# LE1-11.net
KiCad netlist of a schematic drawn in EAGLE
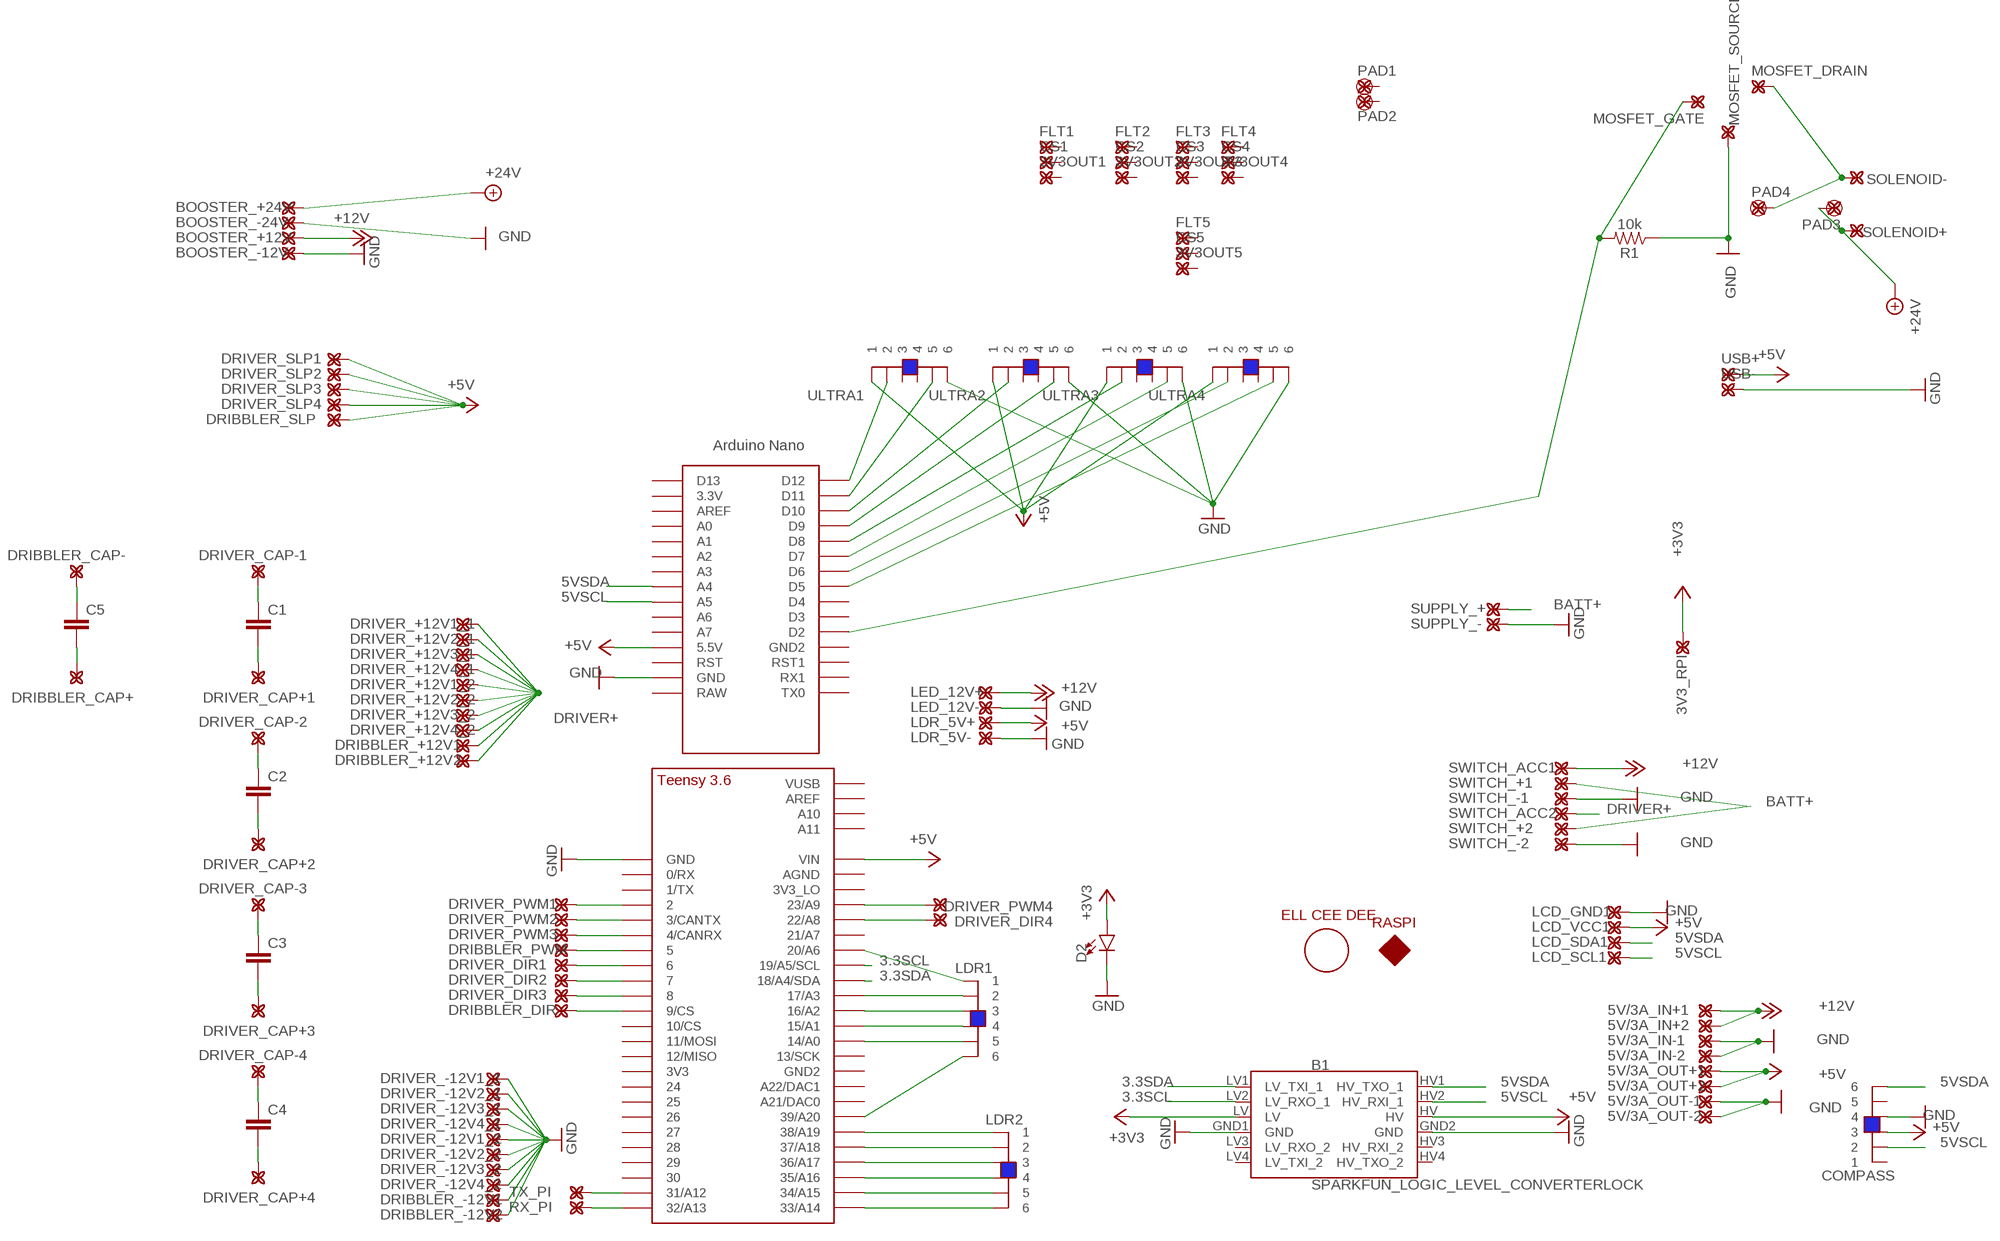
[diagram p0: schematic, sheet 1]

(export (version "E")
  (design (tool "Eeschema 10.0.6"))
  (components
    (comp (ref "3V3OUT1")
      (value "BETTERPAD_2.54")
      (footprint "eagle-import:SUPERIORSIM")
      (libsource (lib "eagle-import") (part "BETTERPAD_2.54"))
    )
    (comp (ref "3V3OUT2")
      (value "BETTERPAD_2.54")
      (footprint "eagle-import:SUPERIORSIM")
      (libsource (lib "eagle-import") (part "BETTERPAD_2.54"))
    )
    (comp (ref "3V3OUT3")
      (value "BETTERPAD_2.54")
      (footprint "eagle-import:SUPERIORSIM")
      (libsource (lib "eagle-import") (part "BETTERPAD_2.54"))
    )
    (comp (ref "3V3OUT4")
      (value "BETTERPAD_2.54")
      (footprint "eagle-import:SUPERIORSIM")
      (libsource (lib "eagle-import") (part "BETTERPAD_2.54"))
    )
    (comp (ref "3V3OUT5")
      (value "BETTERPAD_2.54")
      (footprint "eagle-import:SUPERIORSIM")
      (libsource (lib "eagle-import") (part "BETTERPAD_2.54"))
    )
    (comp (ref "3V3_RPI")
      (value "BETTERPAD_2.54")
      (footprint "eagle-import:SUPERIORSIM")
      (libsource (lib "eagle-import") (part "BETTERPAD_2.54"))
    )
    (comp (ref "5V/3A_IN+1")
      (value "BETTERPAD_2.54")
      (footprint "eagle-import:SUPERIORSIM")
      (libsource (lib "eagle-import") (part "BETTERPAD_2.54"))
    )
    (comp (ref "5V/3A_IN+2")
      (value "BETTERPAD_2.54")
      (footprint "eagle-import:SUPERIORSIM")
      (libsource (lib "eagle-import") (part "BETTERPAD_2.54"))
    )
    (comp (ref "5V/3A_IN-1")
      (value "BETTERPAD_2.54")
      (footprint "eagle-import:SUPERIORSIM")
      (libsource (lib "eagle-import") (part "BETTERPAD_2.54"))
    )
    (comp (ref "5V/3A_IN-2")
      (value "BETTERPAD_2.54")
      (footprint "eagle-import:SUPERIORSIM")
      (libsource (lib "eagle-import") (part "BETTERPAD_2.54"))
    )
    (comp (ref "5V/3A_OUT+1")
      (value "BETTERPAD_2.54")
      (footprint "eagle-import:SUPERIORSIM")
      (libsource (lib "eagle-import") (part "BETTERPAD_2.54"))
    )
    (comp (ref "5V/3A_OUT+2")
      (value "BETTERPAD_2.54")
      (footprint "eagle-import:SUPERIORSIM")
      (libsource (lib "eagle-import") (part "BETTERPAD_2.54"))
    )
    (comp (ref "5V/3A_OUT-1")
      (value "BETTERPAD_2.54")
      (footprint "eagle-import:SUPERIORSIM")
      (libsource (lib "eagle-import") (part "BETTERPAD_2.54"))
    )
    (comp (ref "5V/3A_OUT-2")
      (value "BETTERPAD_2.54")
      (footprint "eagle-import:SUPERIORSIM")
      (libsource (lib "eagle-import") (part "BETTERPAD_2.54"))
    )
    (comp (ref "B1")
      (value "SPARKFUN_LOGIC_LEVEL_CONVERTERLOCK")
      (footprint "eagle-import:SPARKFUN_LOGIC_LEVEL_CONVERTER_LOCK")
      (libsource (lib "eagle-import") (part "SPARKFUN_LOGIC_LEVEL_CONVERTERLOCK"))
    )
    (comp (ref "BOOSTER_+12V")
      (value "BETTERPAD_2.54")
      (footprint "eagle-import:SUPERIORSIM")
      (libsource (lib "eagle-import") (part "BETTERPAD_2.54"))
    )
    (comp (ref "BOOSTER_+24V")
      (value "BETTERPAD_2.54")
      (footprint "eagle-import:SUPERIORSIM")
      (libsource (lib "eagle-import") (part "BETTERPAD_2.54"))
    )
    (comp (ref "BOOSTER_-12V")
      (value "BETTERPAD_2.54")
      (footprint "eagle-import:SUPERIORSIM")
      (libsource (lib "eagle-import") (part "BETTERPAD_2.54"))
    )
    (comp (ref "BOOSTER_-24V")
      (value "BETTERPAD_2.54")
      (footprint "eagle-import:SUPERIORSIM")
      (libsource (lib "eagle-import") (part "BETTERPAD_2.54"))
    )
    (comp (ref "C1")
      (value "C5/7.2")
      (footprint "eagle-import:C5B7.2")
      (libsource (lib "eagle-import") (part "C5/7.2"))
    )
    (comp (ref "C2")
      (value "C5/7.2")
      (footprint "eagle-import:C5B7.2")
      (libsource (lib "eagle-import") (part "C5/7.2"))
    )
    (comp (ref "C3")
      (value "C5/7.2")
      (footprint "eagle-import:C5B7.2")
      (libsource (lib "eagle-import") (part "C5/7.2"))
    )
    (comp (ref "C4")
      (value "C5/7.2")
      (footprint "eagle-import:C5B7.2")
      (libsource (lib "eagle-import") (part "C5/7.2"))
    )
    (comp (ref "C5")
      (value "C5/7.2")
      (footprint "eagle-import:C5B7.2")
      (libsource (lib "eagle-import") (part "C5/7.2"))
    )
    (comp (ref "COMPASS")
      (value "6P6C_FEMALESMD")
      (footprint "eagle-import:6P6C_FEMALE")
      (libsource (lib "eagle-import") (part "6P6C_FEMALESMD"))
    )
    (comp (ref "CS1")
      (value "BETTERPAD_2.54")
      (footprint "eagle-import:SUPERIORSIM")
      (libsource (lib "eagle-import") (part "BETTERPAD_2.54"))
    )
    (comp (ref "CS2")
      (value "BETTERPAD_2.54")
      (footprint "eagle-import:SUPERIORSIM")
      (libsource (lib "eagle-import") (part "BETTERPAD_2.54"))
    )
    (comp (ref "CS3")
      (value "BETTERPAD_2.54")
      (footprint "eagle-import:SUPERIORSIM")
      (libsource (lib "eagle-import") (part "BETTERPAD_2.54"))
    )
    (comp (ref "CS4")
      (value "BETTERPAD_2.54")
      (footprint "eagle-import:SUPERIORSIM")
      (libsource (lib "eagle-import") (part "BETTERPAD_2.54"))
    )
    (comp (ref "CS5")
      (value "BETTERPAD_2.54")
      (footprint "eagle-import:SUPERIORSIM")
      (libsource (lib "eagle-import") (part "BETTERPAD_2.54"))
    )
    (comp (ref "D2")
      (value "LED-3MM-NO_SILK")
      (footprint "eagle-import:LED_3MM-NS")
      (libsource (lib "eagle-import") (part "LED-3MM-NO_SILK"))
    )
    (comp (ref "DRIBBLER_+12V1")
      (value "BETTERPAD_2.54")
      (footprint "eagle-import:SUPERIORSIM")
      (libsource (lib "eagle-import") (part "BETTERPAD_2.54"))
    )
    (comp (ref "DRIBBLER_+12V2")
      (value "BETTERPAD_2.54")
      (footprint "eagle-import:SUPERIORSIM")
      (libsource (lib "eagle-import") (part "BETTERPAD_2.54"))
    )
    (comp (ref "DRIBBLER_-12V1")
      (value "BETTERPAD_2.54")
      (footprint "eagle-import:SUPERIORSIM")
      (libsource (lib "eagle-import") (part "BETTERPAD_2.54"))
    )
    (comp (ref "DRIBBLER_-12V2")
      (value "BETTERPAD_2.54")
      (footprint "eagle-import:SUPERIORSIM")
      (libsource (lib "eagle-import") (part "BETTERPAD_2.54"))
    )
    (comp (ref "DRIBBLER_CAP+")
      (value "BETTERPAD_2.54")
      (footprint "eagle-import:SUPERIORSIM")
      (libsource (lib "eagle-import") (part "BETTERPAD_2.54"))
    )
    (comp (ref "DRIBBLER_CAP-")
      (value "BETTERPAD_2.54")
      (footprint "eagle-import:SUPERIORSIM")
      (libsource (lib "eagle-import") (part "BETTERPAD_2.54"))
    )
    (comp (ref "DRIBBLER_DIR")
      (value "BETTERPAD_2.54")
      (footprint "eagle-import:SUPERIORSIM")
      (libsource (lib "eagle-import") (part "BETTERPAD_2.54"))
    )
    (comp (ref "DRIBBLER_PWM")
      (value "BETTERPAD_2.54")
      (footprint "eagle-import:SUPERIORSIM")
      (libsource (lib "eagle-import") (part "BETTERPAD_2.54"))
    )
    (comp (ref "DRIBBLER_SLP")
      (value "BETTERPAD_2.54")
      (footprint "eagle-import:SUPERIORSIM")
      (libsource (lib "eagle-import") (part "BETTERPAD_2.54"))
    )
    (comp (ref "DRIVER_+12V1_1")
      (value "BETTERPAD_2.54")
      (footprint "eagle-import:SUPERIORSIM")
      (libsource (lib "eagle-import") (part "BETTERPAD_2.54"))
    )
    (comp (ref "DRIVER_+12V1_2")
      (value "BETTERPAD_2.54")
      (footprint "eagle-import:SUPERIORSIM")
      (libsource (lib "eagle-import") (part "BETTERPAD_2.54"))
    )
    (comp (ref "DRIVER_+12V2_1")
      (value "BETTERPAD_2.54")
      (footprint "eagle-import:SUPERIORSIM")
      (libsource (lib "eagle-import") (part "BETTERPAD_2.54"))
    )
    (comp (ref "DRIVER_+12V2_2")
      (value "BETTERPAD_2.54")
      (footprint "eagle-import:SUPERIORSIM")
      (libsource (lib "eagle-import") (part "BETTERPAD_2.54"))
    )
    (comp (ref "DRIVER_+12V3_1")
      (value "BETTERPAD_2.54")
      (footprint "eagle-import:SUPERIORSIM")
      (libsource (lib "eagle-import") (part "BETTERPAD_2.54"))
    )
    (comp (ref "DRIVER_+12V3_2")
      (value "BETTERPAD_2.54")
      (footprint "eagle-import:SUPERIORSIM")
      (libsource (lib "eagle-import") (part "BETTERPAD_2.54"))
    )
    (comp (ref "DRIVER_+12V4_1")
      (value "BETTERPAD_2.54")
      (footprint "eagle-import:SUPERIORSIM")
      (libsource (lib "eagle-import") (part "BETTERPAD_2.54"))
    )
    (comp (ref "DRIVER_+12V4_2")
      (value "BETTERPAD_2.54")
      (footprint "eagle-import:SUPERIORSIM")
      (libsource (lib "eagle-import") (part "BETTERPAD_2.54"))
    )
    (comp (ref "DRIVER_-12V1_1")
      (value "BETTERPAD_2.54")
      (footprint "eagle-import:SUPERIORSIM")
      (libsource (lib "eagle-import") (part "BETTERPAD_2.54"))
    )
    (comp (ref "DRIVER_-12V1_2")
      (value "BETTERPAD_2.54")
      (footprint "eagle-import:SUPERIORSIM")
      (libsource (lib "eagle-import") (part "BETTERPAD_2.54"))
    )
    (comp (ref "DRIVER_-12V2_1")
      (value "BETTERPAD_2.54")
      (footprint "eagle-import:SUPERIORSIM")
      (libsource (lib "eagle-import") (part "BETTERPAD_2.54"))
    )
    (comp (ref "DRIVER_-12V2_2")
      (value "BETTERPAD_2.54")
      (footprint "eagle-import:SUPERIORSIM")
      (libsource (lib "eagle-import") (part "BETTERPAD_2.54"))
    )
    (comp (ref "DRIVER_-12V3_1")
      (value "BETTERPAD_2.54")
      (footprint "eagle-import:SUPERIORSIM")
      (libsource (lib "eagle-import") (part "BETTERPAD_2.54"))
    )
    (comp (ref "DRIVER_-12V3_2")
      (value "BETTERPAD_2.54")
      (footprint "eagle-import:SUPERIORSIM")
      (libsource (lib "eagle-import") (part "BETTERPAD_2.54"))
    )
    (comp (ref "DRIVER_-12V4_1")
      (value "BETTERPAD_2.54")
      (footprint "eagle-import:SUPERIORSIM")
      (libsource (lib "eagle-import") (part "BETTERPAD_2.54"))
    )
    (comp (ref "DRIVER_-12V4_2")
      (value "BETTERPAD_2.54")
      (footprint "eagle-import:SUPERIORSIM")
      (libsource (lib "eagle-import") (part "BETTERPAD_2.54"))
    )
    (comp (ref "DRIVER_CAP+1")
      (value "BETTERPAD_2.54")
      (footprint "eagle-import:SUPERIORSIM")
      (libsource (lib "eagle-import") (part "BETTERPAD_2.54"))
    )
    (comp (ref "DRIVER_CAP+2")
      (value "BETTERPAD_2.54")
      (footprint "eagle-import:SUPERIORSIM")
      (libsource (lib "eagle-import") (part "BETTERPAD_2.54"))
    )
    (comp (ref "DRIVER_CAP+3")
      (value "BETTERPAD_2.54")
      (footprint "eagle-import:SUPERIORSIM")
      (libsource (lib "eagle-import") (part "BETTERPAD_2.54"))
    )
    (comp (ref "DRIVER_CAP+4")
      (value "BETTERPAD_2.54")
      (footprint "eagle-import:SUPERIORSIM")
      (libsource (lib "eagle-import") (part "BETTERPAD_2.54"))
    )
    (comp (ref "DRIVER_CAP-1")
      (value "BETTERPAD_2.54")
      (footprint "eagle-import:SUPERIORSIM")
      (libsource (lib "eagle-import") (part "BETTERPAD_2.54"))
    )
    (comp (ref "DRIVER_CAP-2")
      (value "BETTERPAD_2.54")
      (footprint "eagle-import:SUPERIORSIM")
      (libsource (lib "eagle-import") (part "BETTERPAD_2.54"))
    )
    (comp (ref "DRIVER_CAP-3")
      (value "BETTERPAD_2.54")
      (footprint "eagle-import:SUPERIORSIM")
      (libsource (lib "eagle-import") (part "BETTERPAD_2.54"))
    )
    (comp (ref "DRIVER_CAP-4")
      (value "BETTERPAD_2.54")
      (footprint "eagle-import:SUPERIORSIM")
      (libsource (lib "eagle-import") (part "BETTERPAD_2.54"))
    )
    (comp (ref "DRIVER_DIR1")
      (value "BETTERPAD_2.54")
      (footprint "eagle-import:SUPERIORSIM")
      (libsource (lib "eagle-import") (part "BETTERPAD_2.54"))
    )
    (comp (ref "DRIVER_DIR2")
      (value "BETTERPAD_2.54")
      (footprint "eagle-import:SUPERIORSIM")
      (libsource (lib "eagle-import") (part "BETTERPAD_2.54"))
    )
    (comp (ref "DRIVER_DIR3")
      (value "BETTERPAD_2.54")
      (footprint "eagle-import:SUPERIORSIM")
      (libsource (lib "eagle-import") (part "BETTERPAD_2.54"))
    )
    (comp (ref "DRIVER_DIR4")
      (value "BETTERPAD_2.54")
      (footprint "eagle-import:SUPERIORSIM")
      (libsource (lib "eagle-import") (part "BETTERPAD_2.54"))
    )
    (comp (ref "DRIVER_PWM1")
      (value "BETTERPAD_2.54")
      (footprint "eagle-import:SUPERIORSIM")
      (libsource (lib "eagle-import") (part "BETTERPAD_2.54"))
    )
    (comp (ref "DRIVER_PWM2")
      (value "BETTERPAD_2.54")
      (footprint "eagle-import:SUPERIORSIM")
      (libsource (lib "eagle-import") (part "BETTERPAD_2.54"))
    )
    (comp (ref "DRIVER_PWM3")
      (value "BETTERPAD_2.54")
      (footprint "eagle-import:SUPERIORSIM")
      (libsource (lib "eagle-import") (part "BETTERPAD_2.54"))
    )
    (comp (ref "DRIVER_PWM4")
      (value "BETTERPAD_2.54")
      (footprint "eagle-import:SUPERIORSIM")
      (libsource (lib "eagle-import") (part "BETTERPAD_2.54"))
    )
    (comp (ref "DRIVER_SLP1")
      (value "BETTERPAD_2.54")
      (footprint "eagle-import:SUPERIORSIM")
      (libsource (lib "eagle-import") (part "BETTERPAD_2.54"))
    )
    (comp (ref "DRIVER_SLP2")
      (value "BETTERPAD_2.54")
      (footprint "eagle-import:SUPERIORSIM")
      (libsource (lib "eagle-import") (part "BETTERPAD_2.54"))
    )
    (comp (ref "DRIVER_SLP3")
      (value "BETTERPAD_2.54")
      (footprint "eagle-import:SUPERIORSIM")
      (libsource (lib "eagle-import") (part "BETTERPAD_2.54"))
    )
    (comp (ref "DRIVER_SLP4")
      (value "BETTERPAD_2.54")
      (footprint "eagle-import:SUPERIORSIM")
      (libsource (lib "eagle-import") (part "BETTERPAD_2.54"))
    )
    (comp (ref "FLT1")
      (value "BETTERPAD_2.54")
      (footprint "eagle-import:SUPERIORSIM")
      (libsource (lib "eagle-import") (part "BETTERPAD_2.54"))
    )
    (comp (ref "FLT2")
      (value "BETTERPAD_2.54")
      (footprint "eagle-import:SUPERIORSIM")
      (libsource (lib "eagle-import") (part "BETTERPAD_2.54"))
    )
    (comp (ref "FLT3")
      (value "BETTERPAD_2.54")
      (footprint "eagle-import:SUPERIORSIM")
      (libsource (lib "eagle-import") (part "BETTERPAD_2.54"))
    )
    (comp (ref "FLT4")
      (value "BETTERPAD_2.54")
      (footprint "eagle-import:SUPERIORSIM")
      (libsource (lib "eagle-import") (part "BETTERPAD_2.54"))
    )
    (comp (ref "FLT5")
      (value "BETTERPAD_2.54")
      (footprint "eagle-import:SUPERIORSIM")
      (libsource (lib "eagle-import") (part "BETTERPAD_2.54"))
    )
    (comp (ref "LCD1")
      (value "LCD-16X2SILK")
      (footprint "eagle-import:LCD-16X2")
      (libsource (lib "eagle-import") (part "LCD-16X2SILK"))
    )
    (comp (ref "LCD_GND1")
      (value "BETTERPAD_2.54")
      (footprint "eagle-import:SUPERIORSIM")
      (libsource (lib "eagle-import") (part "BETTERPAD_2.54"))
    )
    (comp (ref "LCD_SCL1")
      (value "BETTERPAD_2.54")
      (footprint "eagle-import:SUPERIORSIM")
      (libsource (lib "eagle-import") (part "BETTERPAD_2.54"))
    )
    (comp (ref "LCD_SDA1")
      (value "BETTERPAD_2.54")
      (footprint "eagle-import:SUPERIORSIM")
      (libsource (lib "eagle-import") (part "BETTERPAD_2.54"))
    )
    (comp (ref "LCD_VCC1")
      (value "BETTERPAD_2.54")
      (footprint "eagle-import:SUPERIORSIM")
      (libsource (lib "eagle-import") (part "BETTERPAD_2.54"))
    )
    (comp (ref "LDR1")
      (value "6P6C_FEMALESMD")
      (footprint "eagle-import:6P6C_FEMALE")
      (libsource (lib "eagle-import") (part "6P6C_FEMALESMD"))
    )
    (comp (ref "LDR2")
      (value "6P6C_FEMALESMD")
      (footprint "eagle-import:6P6C_FEMALE")
      (libsource (lib "eagle-import") (part "6P6C_FEMALESMD"))
    )
    (comp (ref "LDR_5V+")
      (value "BETTERPAD_2.54")
      (footprint "eagle-import:SUPERIORSIM")
      (libsource (lib "eagle-import") (part "BETTERPAD_2.54"))
    )
    (comp (ref "LDR_5V-")
      (value "BETTERPAD_2.54")
      (footprint "eagle-import:SUPERIORSIM")
      (libsource (lib "eagle-import") (part "BETTERPAD_2.54"))
    )
    (comp (ref "LED_12V+")
      (value "BETTERPAD_2.54")
      (footprint "eagle-import:SUPERIORSIM")
      (libsource (lib "eagle-import") (part "BETTERPAD_2.54"))
    )
    (comp (ref "LED_12V-")
      (value "BETTERPAD_2.54")
      (footprint "eagle-import:SUPERIORSIM")
      (libsource (lib "eagle-import") (part "BETTERPAD_2.54"))
    )
    (comp (ref "MOSFET_DRAIN")
      (value "BETTERPAD_2.54")
      (footprint "eagle-import:SUPERIORSIM")
      (libsource (lib "eagle-import") (part "BETTERPAD_2.54"))
    )
    (comp (ref "MOSFET_GATE")
      (value "BETTERPAD_2.54")
      (footprint "eagle-import:SUPERIORSIM")
      (libsource (lib "eagle-import") (part "BETTERPAD_2.54"))
    )
    (comp (ref "MOSFET_SOURCE")
      (value "BETTERPAD_2.54")
      (footprint "eagle-import:SUPERIORSIM")
      (libsource (lib "eagle-import") (part "BETTERPAD_2.54"))
    )
    (comp (ref "PAD1")
      (value "BETTERPAD_2.54/1.5")
      (footprint "eagle-import:1,5")
      (libsource (lib "eagle-import") (part "BETTERPAD_2.54/1.5"))
    )
    (comp (ref "PAD2")
      (value "BETTERPAD_2.54/1.5")
      (footprint "eagle-import:1,5")
      (libsource (lib "eagle-import") (part "BETTERPAD_2.54/1.5"))
    )
    (comp (ref "PAD3")
      (value "BETTERPAD_2.54/1.5")
      (footprint "eagle-import:1,5")
      (libsource (lib "eagle-import") (part "BETTERPAD_2.54/1.5"))
    )
    (comp (ref "PAD4")
      (value "BETTERPAD_2.54/1.5")
      (footprint "eagle-import:1,5")
      (libsource (lib "eagle-import") (part "BETTERPAD_2.54/1.5"))
    )
    (comp (ref "PCB1")
      (value "RPI3")
      (footprint "eagle-import:RPI3")
      (libsource (lib "eagle-import") (part "RPI3"))
    )
    (comp (ref "R1")
      (value "10k")
      (footprint "eagle-import:AXIAL-0.3")
      (libsource (lib "eagle-import") (part "10KOHM-HORIZ-1/4W-1%"))
    )
    (comp (ref "RX_PI")
      (value "BETTERPAD_2.54")
      (footprint "eagle-import:SUPERIORSIM")
      (libsource (lib "eagle-import") (part "BETTERPAD_2.54"))
    )
    (comp (ref "SOLENOID+")
      (value "BETTERPAD_2.54")
      (footprint "eagle-import:SUPERIORSIM")
      (libsource (lib "eagle-import") (part "BETTERPAD_2.54"))
    )
    (comp (ref "SOLENOID-")
      (value "BETTERPAD_2.54")
      (footprint "eagle-import:SUPERIORSIM")
      (libsource (lib "eagle-import") (part "BETTERPAD_2.54"))
    )
    (comp (ref "SUPPLY_+")
      (value "BETTERPAD_2.54")
      (footprint "eagle-import:SUPERIORSIM")
      (libsource (lib "eagle-import") (part "BETTERPAD_2.54"))
    )
    (comp (ref "SUPPLY_-")
      (value "BETTERPAD_2.54")
      (footprint "eagle-import:SUPERIORSIM")
      (libsource (lib "eagle-import") (part "BETTERPAD_2.54"))
    )
    (comp (ref "SWITCH_+1")
      (value "BETTERPAD_2.54")
      (footprint "eagle-import:SUPERIORSIM")
      (libsource (lib "eagle-import") (part "BETTERPAD_2.54"))
    )
    (comp (ref "SWITCH_+2")
      (value "BETTERPAD_2.54")
      (footprint "eagle-import:SUPERIORSIM")
      (libsource (lib "eagle-import") (part "BETTERPAD_2.54"))
    )
    (comp (ref "SWITCH_-1")
      (value "BETTERPAD_2.54")
      (footprint "eagle-import:SUPERIORSIM")
      (libsource (lib "eagle-import") (part "BETTERPAD_2.54"))
    )
    (comp (ref "SWITCH_-2")
      (value "BETTERPAD_2.54")
      (footprint "eagle-import:SUPERIORSIM")
      (libsource (lib "eagle-import") (part "BETTERPAD_2.54"))
    )
    (comp (ref "SWITCH_ACC1")
      (value "BETTERPAD_2.54")
      (footprint "eagle-import:SUPERIORSIM")
      (libsource (lib "eagle-import") (part "BETTERPAD_2.54"))
    )
    (comp (ref "SWITCH_ACC2")
      (value "BETTERPAD_2.54")
      (footprint "eagle-import:SUPERIORSIM")
      (libsource (lib "eagle-import") (part "BETTERPAD_2.54"))
    )
    (comp (ref "TX_PI")
      (value "BETTERPAD_2.54")
      (footprint "eagle-import:SUPERIORSIM")
      (libsource (lib "eagle-import") (part "BETTERPAD_2.54"))
    )
    (comp (ref "U$1")
      (value "TEENSY_3.5/3.6_BASIC")
      (footprint "eagle-import:TEENSY_3.5_3.6_BASIC")
      (libsource (lib "eagle-import") (part "TEENSY_3.5/3.6_BASIC"))
    )
    (comp (ref "U$2")
      (value "NANO")
      (footprint "eagle-import:NANO")
      (libsource (lib "eagle-import") (part "NANO"))
    )
    (comp (ref "ULTRA1")
      (value "6P6C_FEMALESMD")
      (footprint "eagle-import:6P6C_FEMALE")
      (libsource (lib "eagle-import") (part "6P6C_FEMALESMD"))
    )
    (comp (ref "ULTRA2")
      (value "6P6C_FEMALESMD")
      (footprint "eagle-import:6P6C_FEMALE")
      (libsource (lib "eagle-import") (part "6P6C_FEMALESMD"))
    )
    (comp (ref "ULTRA3")
      (value "6P6C_FEMALESMD")
      (footprint "eagle-import:6P6C_FEMALE")
      (libsource (lib "eagle-import") (part "6P6C_FEMALESMD"))
    )
    (comp (ref "ULTRA4")
      (value "6P6C_FEMALESMD")
      (footprint "eagle-import:6P6C_FEMALE")
      (libsource (lib "eagle-import") (part "6P6C_FEMALESMD"))
    )
    (comp (ref "USB+")
      (value "BETTERPAD_2.54")
      (footprint "eagle-import:SUPERIORSIM")
      (libsource (lib "eagle-import") (part "BETTERPAD_2.54"))
    )
    (comp (ref "USB-")
      (value "BETTERPAD_2.54")
      (footprint "eagle-import:SUPERIORSIM")
      (libsource (lib "eagle-import") (part "BETTERPAD_2.54"))
    )
  )
  (nets
    (net (code "1") (name "+3V3") (class "Default")
      (node (ref "3V3_RPI") (pin ".") (pinfunction "P_.") (pintype "passive"))
      (node (ref "B1") (pin "LV") (pinfunction "LV_LV") (pintype "power_in"))
      (node (ref "D2") (pin "A") (pinfunction "A_A") (pintype "passive"))
    )
    (net (code "2") (name "+5V") (class "Default")
      (node (ref "5V/3A_OUT+1") (pin ".") (pinfunction "P_.") (pintype "passive"))
      (node (ref "5V/3A_OUT+2") (pin ".") (pinfunction "P_.") (pintype "passive"))
      (node (ref "B1") (pin "HV") (pinfunction "HV_HV") (pintype "power_in"))
      (node (ref "COMPASS") (pin "3") (pinfunction "3_3") (pintype "bidirectional"))
      (node (ref "DRIBBLER_SLP") (pin ".") (pinfunction "P_.") (pintype "passive"))
      (node (ref "DRIVER_SLP1") (pin ".") (pinfunction "P_.") (pintype "passive"))
      (node (ref "DRIVER_SLP2") (pin ".") (pinfunction "P_.") (pintype "passive"))
      (node (ref "DRIVER_SLP3") (pin ".") (pinfunction "P_.") (pintype "passive"))
      (node (ref "DRIVER_SLP4") (pin ".") (pinfunction "P_.") (pintype "passive"))
      (node (ref "LCD_VCC1") (pin ".") (pinfunction "P_.") (pintype "passive"))
      (node (ref "LDR_5V+") (pin ".") (pinfunction "P_.") (pintype "passive"))
      (node (ref "U$1") (pin "VIN") (pinfunction "VIN_VIN") (pintype "bidirectional"))
      (node (ref "U$2") (pin "5V") (pinfunction "5.5V_5V") (pintype "bidirectional"))
      (node (ref "ULTRA1") (pin "1") (pinfunction "1_1") (pintype "bidirectional"))
      (node (ref "ULTRA2") (pin "1") (pinfunction "1_1") (pintype "bidirectional"))
      (node (ref "ULTRA3") (pin "1") (pinfunction "1_1") (pintype "bidirectional"))
      (node (ref "ULTRA4") (pin "1") (pinfunction "1_1") (pintype "bidirectional"))
      (node (ref "USB+") (pin ".") (pinfunction "P_.") (pintype "passive"))
    )
    (net (code "3") (name "+12V") (class "Default")
      (node (ref "5V/3A_IN+1") (pin ".") (pinfunction "P_.") (pintype "passive"))
      (node (ref "5V/3A_IN+2") (pin ".") (pinfunction "P_.") (pintype "passive"))
      (node (ref "BOOSTER_+12V") (pin ".") (pinfunction "P_.") (pintype "passive"))
      (node (ref "LED_12V+") (pin ".") (pinfunction "P_.") (pintype "passive"))
      (node (ref "SWITCH_ACC1") (pin ".") (pinfunction "P_.") (pintype "passive"))
    )
    (net (code "4") (name "+24V") (class "Default")
      (node (ref "BOOSTER_+24V") (pin ".") (pinfunction "P_.") (pintype "passive"))
      (node (ref "PAD3") (pin "P$1") (pinfunction "P_P$1") (pintype "passive"))
      (node (ref "SOLENOID+") (pin ".") (pinfunction "P_.") (pintype "passive"))
    )
    (net (code "5") (name "/3.3SCL") (class "Default")
      (node (ref "B1") (pin "LV2") (pinfunction "LV_RXO_1_LV2") (pintype "bidirectional"))
      (node (ref "U$1") (pin "19/A5/SCL") (pinfunction "19/A5/SCL_19/A5/SCL") (pintype "bidirectional"))
    )
    (net (code "6") (name "/3.3SDA") (class "Default")
      (node (ref "B1") (pin "LV1") (pinfunction "LV_TXI_1_LV1") (pintype "bidirectional"))
      (node (ref "U$1") (pin "18/A4/SDA") (pinfunction "18/A4/SDA_18/A4/SDA") (pintype "bidirectional"))
    )
    (net (code "7") (name "/5VSCL") (class "Default")
      (node (ref "B1") (pin "HV2") (pinfunction "HV_RXI_1_HV2") (pintype "bidirectional"))
      (node (ref "COMPASS") (pin "2") (pinfunction "2_2") (pintype "bidirectional"))
      (node (ref "LCD_SCL1") (pin ".") (pinfunction "P_.") (pintype "passive"))
      (node (ref "U$2") (pin "A5") (pinfunction "A5_A5") (pintype "bidirectional"))
    )
    (net (code "8") (name "/5VSDA") (class "Default")
      (node (ref "B1") (pin "HV1") (pinfunction "HV_TXO_1_HV1") (pintype "bidirectional"))
      (node (ref "COMPASS") (pin "6") (pinfunction "6_6") (pintype "bidirectional"))
      (node (ref "LCD_SDA1") (pin ".") (pinfunction "P_.") (pintype "passive"))
      (node (ref "U$2") (pin "A4") (pinfunction "A4_A4") (pintype "bidirectional"))
    )
    (net (code "9") (name "/BATT+") (class "Default")
      (node (ref "SUPPLY_+") (pin ".") (pinfunction "P_.") (pintype "passive"))
      (node (ref "SWITCH_+1") (pin ".") (pinfunction "P_.") (pintype "passive"))
      (node (ref "SWITCH_+2") (pin ".") (pinfunction "P_.") (pintype "passive"))
    )
    (net (code "10") (name "/DRIVER+") (class "Default")
      (node (ref "DRIBBLER_+12V1") (pin ".") (pinfunction "P_.") (pintype "passive"))
      (node (ref "DRIBBLER_+12V2") (pin ".") (pinfunction "P_.") (pintype "passive"))
      (node (ref "DRIVER_+12V1_1") (pin ".") (pinfunction "P_.") (pintype "passive"))
      (node (ref "DRIVER_+12V1_2") (pin ".") (pinfunction "P_.") (pintype "passive"))
      (node (ref "DRIVER_+12V2_1") (pin ".") (pinfunction "P_.") (pintype "passive"))
      (node (ref "DRIVER_+12V2_2") (pin ".") (pinfunction "P_.") (pintype "passive"))
      (node (ref "DRIVER_+12V3_1") (pin ".") (pinfunction "P_.") (pintype "passive"))
      (node (ref "DRIVER_+12V3_2") (pin ".") (pinfunction "P_.") (pintype "passive"))
      (node (ref "DRIVER_+12V4_1") (pin ".") (pinfunction "P_.") (pintype "passive"))
      (node (ref "DRIVER_+12V4_2") (pin ".") (pinfunction "P_.") (pintype "passive"))
      (node (ref "SWITCH_ACC2") (pin ".") (pinfunction "P_.") (pintype "passive"))
    )
    (net (code "11") (name "GND") (class "Default")
      (node (ref "5V/3A_IN-1") (pin ".") (pinfunction "P_.") (pintype "passive"))
      (node (ref "5V/3A_IN-2") (pin ".") (pinfunction "P_.") (pintype "passive"))
      (node (ref "5V/3A_OUT-1") (pin ".") (pinfunction "P_.") (pintype "passive"))
      (node (ref "5V/3A_OUT-2") (pin ".") (pinfunction "P_.") (pintype "passive"))
      (node (ref "B1") (pin "GND1") (pinfunction "GND_GND1") (pintype "power_in"))
      (node (ref "B1") (pin "GND2") (pinfunction "GND_GND2") (pintype "power_in"))
      (node (ref "BOOSTER_-12V") (pin ".") (pinfunction "P_.") (pintype "passive"))
      (node (ref "BOOSTER_-24V") (pin ".") (pinfunction "P_.") (pintype "passive"))
      (node (ref "COMPASS") (pin "4") (pinfunction "4_4") (pintype "bidirectional"))
      (node (ref "D2") (pin "K") (pinfunction "C_K") (pintype "passive"))
      (node (ref "DRIBBLER_-12V1") (pin ".") (pinfunction "P_.") (pintype "passive"))
      (node (ref "DRIBBLER_-12V2") (pin ".") (pinfunction "P_.") (pintype "passive"))
      (node (ref "DRIVER_-12V1_1") (pin ".") (pinfunction "P_.") (pintype "passive"))
      (node (ref "DRIVER_-12V1_2") (pin ".") (pinfunction "P_.") (pintype "passive"))
      (node (ref "DRIVER_-12V2_1") (pin ".") (pinfunction "P_.") (pintype "passive"))
      (node (ref "DRIVER_-12V2_2") (pin ".") (pinfunction "P_.") (pintype "passive"))
      (node (ref "DRIVER_-12V3_1") (pin ".") (pinfunction "P_.") (pintype "passive"))
      (node (ref "DRIVER_-12V3_2") (pin ".") (pinfunction "P_.") (pintype "passive"))
      (node (ref "DRIVER_-12V4_1") (pin ".") (pinfunction "P_.") (pintype "passive"))
      (node (ref "DRIVER_-12V4_2") (pin ".") (pinfunction "P_.") (pintype "passive"))
      (node (ref "LCD_GND1") (pin ".") (pinfunction "P_.") (pintype "passive"))
      (node (ref "LDR_5V-") (pin ".") (pinfunction "P_.") (pintype "passive"))
      (node (ref "LED_12V-") (pin ".") (pinfunction "P_.") (pintype "passive"))
      (node (ref "MOSFET_SOURCE") (pin ".") (pinfunction "P_.") (pintype "passive"))
      (node (ref "R1") (pin "P$1") (pinfunction "1_P$1") (pintype "passive"))
      (node (ref "SUPPLY_-") (pin ".") (pinfunction "P_.") (pintype "passive"))
      (node (ref "SWITCH_-1") (pin ".") (pinfunction "P_.") (pintype "passive"))
      (node (ref "SWITCH_-2") (pin ".") (pinfunction "P_.") (pintype "passive"))
      (node (ref "U$1") (pin "GND") (pinfunction "GND_GND") (pintype "bidirectional"))
      (node (ref "U$2") (pin "GND") (pinfunction "GND_GND") (pintype "bidirectional"))
      (node (ref "ULTRA1") (pin "6") (pinfunction "6_6") (pintype "bidirectional"))
      (node (ref "ULTRA2") (pin "6") (pinfunction "6_6") (pintype "bidirectional"))
      (node (ref "ULTRA3") (pin "6") (pinfunction "6_6") (pintype "bidirectional"))
      (node (ref "ULTRA4") (pin "6") (pinfunction "6_6") (pintype "bidirectional"))
      (node (ref "USB-") (pin ".") (pinfunction "P_.") (pintype "passive"))
    )
    (net (code "12") (name "Net-(DRIBBLER_CAP+-P)") (class "Default")
      (node (ref "C5") (pin "2") (pinfunction "2_2") (pintype "passive"))
      (node (ref "DRIBBLER_CAP+") (pin ".") (pinfunction "P_.") (pintype "passive"))
    )
    (net (code "13") (name "Net-(DRIBBLER_CAP--P)") (class "Default")
      (node (ref "C5") (pin "1") (pinfunction "1_1") (pintype "passive"))
      (node (ref "DRIBBLER_CAP-") (pin ".") (pinfunction "P_.") (pintype "passive"))
    )
    (net (code "14") (name "Net-(DRIBBLER_DIR-P)") (class "Default")
      (node (ref "DRIBBLER_DIR") (pin ".") (pinfunction "P_.") (pintype "passive"))
      (node (ref "U$1") (pin "9/CS") (pinfunction "9/CS_9/CS") (pintype "bidirectional"))
    )
    (net (code "15") (name "Net-(DRIBBLER_PWM-P)") (class "Default")
      (node (ref "DRIBBLER_PWM") (pin ".") (pinfunction "P_.") (pintype "passive"))
      (node (ref "U$1") (pin "5") (pinfunction "5_5") (pintype "bidirectional"))
    )
    (net (code "16") (name "Net-(DRIVER_CAP+1-P)") (class "Default")
      (node (ref "C1") (pin "2") (pinfunction "2_2") (pintype "passive"))
      (node (ref "DRIVER_CAP+1") (pin ".") (pinfunction "P_.") (pintype "passive"))
    )
    (net (code "17") (name "Net-(DRIVER_CAP+2-P)") (class "Default")
      (node (ref "C2") (pin "2") (pinfunction "2_2") (pintype "passive"))
      (node (ref "DRIVER_CAP+2") (pin ".") (pinfunction "P_.") (pintype "passive"))
    )
    (net (code "18") (name "Net-(DRIVER_CAP+3-P)") (class "Default")
      (node (ref "C3") (pin "2") (pinfunction "2_2") (pintype "passive"))
      (node (ref "DRIVER_CAP+3") (pin ".") (pinfunction "P_.") (pintype "passive"))
    )
    (net (code "19") (name "Net-(DRIVER_CAP+4-P)") (class "Default")
      (node (ref "C4") (pin "2") (pinfunction "2_2") (pintype "passive"))
      (node (ref "DRIVER_CAP+4") (pin ".") (pinfunction "P_.") (pintype "passive"))
    )
    (net (code "20") (name "Net-(DRIVER_CAP-1-P)") (class "Default")
      (node (ref "C1") (pin "1") (pinfunction "1_1") (pintype "passive"))
      (node (ref "DRIVER_CAP-1") (pin ".") (pinfunction "P_.") (pintype "passive"))
    )
    (net (code "21") (name "Net-(DRIVER_CAP-2-P)") (class "Default")
      (node (ref "C2") (pin "1") (pinfunction "1_1") (pintype "passive"))
      (node (ref "DRIVER_CAP-2") (pin ".") (pinfunction "P_.") (pintype "passive"))
    )
    (net (code "22") (name "Net-(DRIVER_CAP-3-P)") (class "Default")
      (node (ref "C3") (pin "1") (pinfunction "1_1") (pintype "passive"))
      (node (ref "DRIVER_CAP-3") (pin ".") (pinfunction "P_.") (pintype "passive"))
    )
    (net (code "23") (name "Net-(DRIVER_CAP-4-P)") (class "Default")
      (node (ref "C4") (pin "1") (pinfunction "1_1") (pintype "passive"))
      (node (ref "DRIVER_CAP-4") (pin ".") (pinfunction "P_.") (pintype "passive"))
    )
    (net (code "24") (name "Net-(DRIVER_DIR1-P)") (class "Default")
      (node (ref "DRIVER_DIR1") (pin ".") (pinfunction "P_.") (pintype "passive"))
      (node (ref "U$1") (pin "6") (pinfunction "6_6") (pintype "bidirectional"))
    )
    (net (code "25") (name "Net-(DRIVER_DIR2-P)") (class "Default")
      (node (ref "DRIVER_DIR2") (pin ".") (pinfunction "P_.") (pintype "passive"))
      (node (ref "U$1") (pin "7") (pinfunction "7_7") (pintype "bidirectional"))
    )
    (net (code "26") (name "Net-(DRIVER_DIR3-P)") (class "Default")
      (node (ref "DRIVER_DIR3") (pin ".") (pinfunction "P_.") (pintype "passive"))
      (node (ref "U$1") (pin "8") (pinfunction "8_8") (pintype "bidirectional"))
    )
    (net (code "27") (name "Net-(DRIVER_DIR4-P)") (class "Default")
      (node (ref "DRIVER_DIR4") (pin ".") (pinfunction "P_.") (pintype "passive"))
      (node (ref "U$1") (pin "22/A8") (pinfunction "22/A8_22/A8") (pintype "bidirectional"))
    )
    (net (code "28") (name "Net-(DRIVER_PWM1-P)") (class "Default")
      (node (ref "DRIVER_PWM1") (pin ".") (pinfunction "P_.") (pintype "passive"))
      (node (ref "U$1") (pin "2") (pinfunction "2_2") (pintype "bidirectional"))
    )
    (net (code "29") (name "Net-(DRIVER_PWM2-P)") (class "Default")
      (node (ref "DRIVER_PWM2") (pin ".") (pinfunction "P_.") (pintype "passive"))
      (node (ref "U$1") (pin "3/CANTX") (pinfunction "3/CANTX_3/CANTX") (pintype "bidirectional"))
    )
    (net (code "30") (name "Net-(DRIVER_PWM3-P)") (class "Default")
      (node (ref "DRIVER_PWM3") (pin ".") (pinfunction "P_.") (pintype "passive"))
      (node (ref "U$1") (pin "4/CANRX") (pinfunction "4/CANRX_4/CANRX") (pintype "bidirectional"))
    )
    (net (code "31") (name "Net-(DRIVER_PWM4-P)") (class "Default")
      (node (ref "DRIVER_PWM4") (pin ".") (pinfunction "P_.") (pintype "passive"))
      (node (ref "U$1") (pin "23/A9") (pinfunction "23/A9_23/A9") (pintype "bidirectional"))
    )
    (net (code "32") (name "Net-(LDR1-Pad1)") (class "Default")
      (node (ref "LDR1") (pin "1") (pinfunction "1_1") (pintype "bidirectional"))
      (node (ref "U$1") (pin "20/A6") (pinfunction "20/A6_20/A6") (pintype "bidirectional"))
    )
    (net (code "33") (name "Net-(LDR1-Pad2)") (class "Default")
      (node (ref "LDR1") (pin "2") (pinfunction "2_2") (pintype "bidirectional"))
      (node (ref "U$1") (pin "17/A3") (pinfunction "17/A3_17/A3") (pintype "bidirectional"))
    )
    (net (code "34") (name "Net-(LDR1-Pad3)") (class "Default")
      (node (ref "LDR1") (pin "3") (pinfunction "3_3") (pintype "bidirectional"))
      (node (ref "U$1") (pin "16/A2") (pinfunction "16/A2_16/A2") (pintype "bidirectional"))
    )
    (net (code "35") (name "Net-(LDR1-Pad4)") (class "Default")
      (node (ref "LDR1") (pin "4") (pinfunction "4_4") (pintype "bidirectional"))
      (node (ref "U$1") (pin "15/A1") (pinfunction "15/A1_15/A1") (pintype "bidirectional"))
    )
    (net (code "36") (name "Net-(LDR1-Pad5)") (class "Default")
      (node (ref "LDR1") (pin "5") (pinfunction "5_5") (pintype "bidirectional"))
      (node (ref "U$1") (pin "14/A0") (pinfunction "14/A0_14/A0") (pintype "bidirectional"))
    )
    (net (code "37") (name "Net-(LDR1-Pad6)") (class "Default")
      (node (ref "LDR1") (pin "6") (pinfunction "6_6") (pintype "bidirectional"))
      (node (ref "U$1") (pin "39/A20") (pinfunction "39/A20_39/A20") (pintype "bidirectional"))
    )
    (net (code "38") (name "Net-(LDR2-Pad1)") (class "Default")
      (node (ref "LDR2") (pin "1") (pinfunction "1_1") (pintype "bidirectional"))
      (node (ref "U$1") (pin "38/A19") (pinfunction "38/A19_38/A19") (pintype "bidirectional"))
    )
    (net (code "39") (name "Net-(LDR2-Pad2)") (class "Default")
      (node (ref "LDR2") (pin "2") (pinfunction "2_2") (pintype "bidirectional"))
      (node (ref "U$1") (pin "37/A18") (pinfunction "37/A18_37/A18") (pintype "bidirectional"))
    )
    (net (code "40") (name "Net-(LDR2-Pad3)") (class "Default")
      (node (ref "LDR2") (pin "3") (pinfunction "3_3") (pintype "bidirectional"))
      (node (ref "U$1") (pin "36/A17") (pinfunction "36/A17_36/A17") (pintype "bidirectional"))
    )
    (net (code "41") (name "Net-(LDR2-Pad4)") (class "Default")
      (node (ref "LDR2") (pin "4") (pinfunction "4_4") (pintype "bidirectional"))
      (node (ref "U$1") (pin "35/A16") (pinfunction "35/A16_35/A16") (pintype "bidirectional"))
    )
    (net (code "42") (name "Net-(LDR2-Pad5)") (class "Default")
      (node (ref "LDR2") (pin "5") (pinfunction "5_5") (pintype "bidirectional"))
      (node (ref "U$1") (pin "34/A15") (pinfunction "34/A15_34/A15") (pintype "bidirectional"))
    )
    (net (code "43") (name "Net-(LDR2-Pad6)") (class "Default")
      (node (ref "LDR2") (pin "6") (pinfunction "6_6") (pintype "bidirectional"))
      (node (ref "U$1") (pin "33/A14") (pinfunction "33/A14_33/A14") (pintype "bidirectional"))
    )
    (net (code "44") (name "Net-(MOSFET_DRAIN-P)") (class "Default")
      (node (ref "MOSFET_DRAIN") (pin ".") (pinfunction "P_.") (pintype "passive"))
      (node (ref "PAD4") (pin "P$1") (pinfunction "P_P$1") (pintype "passive"))
      (node (ref "SOLENOID-") (pin ".") (pinfunction "P_.") (pintype "passive"))
    )
    (net (code "45") (name "Net-(MOSFET_GATE-P)") (class "Default")
      (node (ref "MOSFET_GATE") (pin ".") (pinfunction "P_.") (pintype "passive"))
      (node (ref "R1") (pin "P$2") (pinfunction "2_P$2") (pintype "passive"))
      (node (ref "U$2") (pin "D2") (pinfunction "D2_D2") (pintype "bidirectional"))
    )
    (net (code "46") (name "Net-(RX_PI-P)") (class "Default")
      (node (ref "RX_PI") (pin ".") (pinfunction "P_.") (pintype "passive"))
      (node (ref "U$1") (pin "32/A13") (pinfunction "32/A13_32/A13") (pintype "bidirectional"))
    )
    (net (code "47") (name "Net-(TX_PI-P)") (class "Default")
      (node (ref "TX_PI") (pin ".") (pinfunction "P_.") (pintype "passive"))
      (node (ref "U$1") (pin "31/A12") (pinfunction "31/A12_31/A12") (pintype "bidirectional"))
    )
    (net (code "48") (name "Net-(U$2-PadD5)") (class "Default")
      (node (ref "U$2") (pin "D5") (pinfunction "D5_D5") (pintype "bidirectional"))
      (node (ref "ULTRA4") (pin "5") (pinfunction "5_5") (pintype "bidirectional"))
    )
    (net (code "49") (name "Net-(U$2-PadD6)") (class "Default")
      (node (ref "U$2") (pin "D6") (pinfunction "D6_D6") (pintype "bidirectional"))
      (node (ref "ULTRA4") (pin "2") (pinfunction "2_2") (pintype "bidirectional"))
    )
    (net (code "50") (name "Net-(U$2-PadD7)") (class "Default")
      (node (ref "U$2") (pin "D7") (pinfunction "D7_D7") (pintype "bidirectional"))
      (node (ref "ULTRA3") (pin "5") (pinfunction "5_5") (pintype "bidirectional"))
    )
    (net (code "51") (name "Net-(U$2-PadD8)") (class "Default")
      (node (ref "U$2") (pin "D8") (pinfunction "D8_D8") (pintype "bidirectional"))
      (node (ref "ULTRA3") (pin "2") (pinfunction "2_2") (pintype "bidirectional"))
    )
    (net (code "52") (name "Net-(U$2-PadD9)") (class "Default")
      (node (ref "U$2") (pin "D9") (pinfunction "D9_D9") (pintype "bidirectional"))
      (node (ref "ULTRA2") (pin "5") (pinfunction "5_5") (pintype "bidirectional"))
    )
    (net (code "53") (name "Net-(U$2-PadD10)") (class "Default")
      (node (ref "U$2") (pin "D10") (pinfunction "D10_D10") (pintype "bidirectional"))
      (node (ref "ULTRA2") (pin "2") (pinfunction "2_2") (pintype "bidirectional"))
    )
    (net (code "54") (name "Net-(U$2-PadD11)") (class "Default")
      (node (ref "U$2") (pin "D11") (pinfunction "D11_D11") (pintype "bidirectional"))
      (node (ref "ULTRA1") (pin "5") (pinfunction "5_5") (pintype "bidirectional"))
    )
    (net (code "55") (name "Net-(U$2-PadD12)") (class "Default")
      (node (ref "U$2") (pin "D12") (pinfunction "D12_D12") (pintype "bidirectional"))
      (node (ref "ULTRA1") (pin "2") (pinfunction "2_2") (pintype "bidirectional"))
    )
    (net (code "56") (name "unconnected-(3V3OUT1-P-Pad.)") (class "Default")
      (node (ref "3V3OUT1") (pin ".") (pinfunction "P_.") (pintype "passive"))
    )
    (net (code "57") (name "unconnected-(3V3OUT2-P-Pad.)") (class "Default")
      (node (ref "3V3OUT2") (pin ".") (pinfunction "P_.") (pintype "passive"))
    )
    (net (code "58") (name "unconnected-(3V3OUT3-P-Pad.)") (class "Default")
      (node (ref "3V3OUT3") (pin ".") (pinfunction "P_.") (pintype "passive"))
    )
    (net (code "59") (name "unconnected-(3V3OUT4-P-Pad.)") (class "Default")
      (node (ref "3V3OUT4") (pin ".") (pinfunction "P_.") (pintype "passive"))
    )
    (net (code "60") (name "unconnected-(3V3OUT5-P-Pad.)") (class "Default")
      (node (ref "3V3OUT5") (pin ".") (pinfunction "P_.") (pintype "passive"))
    )
    (net (code "61") (name "unconnected-(B1-HV_RXI_2-PadHV3)") (class "Default")
      (node (ref "B1") (pin "HV3") (pinfunction "HV_RXI_2_HV3") (pintype "bidirectional"))
    )
    (net (code "62") (name "unconnected-(B1-HV_TXO_2-PadHV4)") (class "Default")
      (node (ref "B1") (pin "HV4") (pinfunction "HV_TXO_2_HV4") (pintype "bidirectional"))
    )
    (net (code "63") (name "unconnected-(B1-LV_RXO_2-PadLV3)") (class "Default")
      (node (ref "B1") (pin "LV3") (pinfunction "LV_RXO_2_LV3") (pintype "bidirectional"))
    )
    (net (code "64") (name "unconnected-(B1-LV_TXI_2-PadLV4)") (class "Default")
      (node (ref "B1") (pin "LV4") (pinfunction "LV_TXI_2_LV4") (pintype "bidirectional"))
    )
    (net (code "65") (name "unconnected-(COMPASS-Pad1)") (class "Default")
      (node (ref "COMPASS") (pin "1") (pinfunction "1_1") (pintype "bidirectional"))
    )
    (net (code "66") (name "unconnected-(COMPASS-Pad5)") (class "Default")
      (node (ref "COMPASS") (pin "5") (pinfunction "5_5") (pintype "bidirectional"))
    )
    (net (code "67") (name "unconnected-(CS1-P-Pad.)") (class "Default")
      (node (ref "CS1") (pin ".") (pinfunction "P_.") (pintype "passive"))
    )
    (net (code "68") (name "unconnected-(CS2-P-Pad.)") (class "Default")
      (node (ref "CS2") (pin ".") (pinfunction "P_.") (pintype "passive"))
    )
    (net (code "69") (name "unconnected-(CS3-P-Pad.)") (class "Default")
      (node (ref "CS3") (pin ".") (pinfunction "P_.") (pintype "passive"))
    )
    (net (code "70") (name "unconnected-(CS4-P-Pad.)") (class "Default")
      (node (ref "CS4") (pin ".") (pinfunction "P_.") (pintype "passive"))
    )
    (net (code "71") (name "unconnected-(CS5-P-Pad.)") (class "Default")
      (node (ref "CS5") (pin ".") (pinfunction "P_.") (pintype "passive"))
    )
    (net (code "72") (name "unconnected-(FLT1-P-Pad.)") (class "Default")
      (node (ref "FLT1") (pin ".") (pinfunction "P_.") (pintype "passive"))
    )
    (net (code "73") (name "unconnected-(FLT2-P-Pad.)") (class "Default")
      (node (ref "FLT2") (pin ".") (pinfunction "P_.") (pintype "passive"))
    )
    (net (code "74") (name "unconnected-(FLT3-P-Pad.)") (class "Default")
      (node (ref "FLT3") (pin ".") (pinfunction "P_.") (pintype "passive"))
    )
    (net (code "75") (name "unconnected-(FLT4-P-Pad.)") (class "Default")
      (node (ref "FLT4") (pin ".") (pinfunction "P_.") (pintype "passive"))
    )
    (net (code "76") (name "unconnected-(FLT5-P-Pad.)") (class "Default")
      (node (ref "FLT5") (pin ".") (pinfunction "P_.") (pintype "passive"))
    )
    (net (code "77") (name "unconnected-(PAD1-P-PadP$1)") (class "Default")
      (node (ref "PAD1") (pin "P$1") (pinfunction "P_P$1") (pintype "passive"))
    )
    (net (code "78") (name "unconnected-(PAD2-P-PadP$1)") (class "Default")
      (node (ref "PAD2") (pin "P$1") (pinfunction "P_P$1") (pintype "passive"))
    )
    (net (code "79") (name "unconnected-(U$1-A21{slash}DAC0-Pad21{slash}DAC0)") (class "Default")
      (node (ref "U$1") (pin "21/DAC0") (pinfunction "A21/DAC0_21/DAC0") (pintype "bidirectional"))
    )
    (net (code "80") (name "unconnected-(U$1-Pad0{slash}RX)") (class "Default")
      (node (ref "U$1") (pin "0/RX") (pinfunction "0/RX_0/RX") (pintype "bidirectional"))
    )
    (net (code "81") (name "unconnected-(U$1-Pad1{slash}TX)") (class "Default")
      (node (ref "U$1") (pin "1/TX") (pinfunction "1/TX_1/TX") (pintype "bidirectional"))
    )
    (net (code "82") (name "unconnected-(U$1-Pad3V3)") (class "Default")
      (node (ref "U$1") (pin "3V3") (pinfunction "3V3_3V3") (pintype "bidirectional"))
    )
    (net (code "83") (name "unconnected-(U$1-Pad3V3_LO)") (class "Default")
      (node (ref "U$1") (pin "3V3_LO") (pinfunction "3V3_LO_3V3_LO") (pintype "bidirectional"))
    )
    (net (code "84") (name "unconnected-(U$1-Pad10{slash}CS)") (class "Default")
      (node (ref "U$1") (pin "10/CS") (pinfunction "10/CS_10/CS") (pintype "bidirectional"))
    )
    (net (code "85") (name "unconnected-(U$1-Pad11{slash}MOSI)") (class "Default")
      (node (ref "U$1") (pin "11/MOSI") (pinfunction "11/MOSI_11/MOSI") (pintype "bidirectional"))
    )
    (net (code "86") (name "unconnected-(U$1-Pad12{slash}MISO)") (class "Default")
      (node (ref "U$1") (pin "12/MISO") (pinfunction "12/MISO_12/MISO") (pintype "bidirectional"))
    )
    (net (code "87") (name "unconnected-(U$1-Pad13{slash}SCK)") (class "Default")
      (node (ref "U$1") (pin "13/SCK") (pinfunction "13/SCK_13/SCK") (pintype "bidirectional"))
    )
    (net (code "88") (name "unconnected-(U$1-Pad21{slash}A7)") (class "Default")
      (node (ref "U$1") (pin "21/A7") (pinfunction "21/A7_21/A7") (pintype "bidirectional"))
    )
    (net (code "89") (name "unconnected-(U$1-Pad24)") (class "Default")
      (node (ref "U$1") (pin "24") (pinfunction "24_24") (pintype "bidirectional"))
    )
    (net (code "90") (name "unconnected-(U$1-Pad25)") (class "Default")
      (node (ref "U$1") (pin "25") (pinfunction "25_25") (pintype "bidirectional"))
    )
    (net (code "91") (name "unconnected-(U$1-Pad26)") (class "Default")
      (node (ref "U$1") (pin "26") (pinfunction "26_26") (pintype "bidirectional"))
    )
    (net (code "92") (name "unconnected-(U$1-Pad27)") (class "Default")
      (node (ref "U$1") (pin "27") (pinfunction "27_27") (pintype "bidirectional"))
    )
    (net (code "93") (name "unconnected-(U$1-Pad28)") (class "Default")
      (node (ref "U$1") (pin "28") (pinfunction "28_28") (pintype "bidirectional"))
    )
    (net (code "94") (name "unconnected-(U$1-Pad29)") (class "Default")
      (node (ref "U$1") (pin "29") (pinfunction "29_29") (pintype "bidirectional"))
    )
    (net (code "95") (name "unconnected-(U$1-Pad30)") (class "Default")
      (node (ref "U$1") (pin "30") (pinfunction "30_30") (pintype "bidirectional"))
    )
    (net (code "96") (name "unconnected-(U$1-PadA10)") (class "Default")
      (node (ref "U$1") (pin "A10") (pinfunction "A10_A10") (pintype "bidirectional"))
    )
    (net (code "97") (name "unconnected-(U$1-PadA11)") (class "Default")
      (node (ref "U$1") (pin "A11") (pinfunction "A11_A11") (pintype "bidirectional"))
    )
    (net (code "98") (name "unconnected-(U$1-PadA22{slash}DAC1)") (class "Default")
      (node (ref "U$1") (pin "A22/DAC1") (pinfunction "A22/DAC1_A22/DAC1") (pintype "bidirectional"))
    )
    (net (code "99") (name "unconnected-(U$1-PadAGND)") (class "Default")
      (node (ref "U$1") (pin "AGND") (pinfunction "AGND_AGND") (pintype "bidirectional"))
    )
    (net (code "100") (name "unconnected-(U$1-PadAREF)") (class "Default")
      (node (ref "U$1") (pin "AREF") (pinfunction "AREF_AREF") (pintype "bidirectional"))
    )
    (net (code "101") (name "unconnected-(U$1-PadGND2)") (class "Default")
      (node (ref "U$1") (pin "GND2") (pinfunction "GND2_GND2") (pintype "bidirectional"))
    )
    (net (code "102") (name "unconnected-(U$1-PadVUSB)") (class "Default")
      (node (ref "U$1") (pin "VUSB") (pinfunction "VUSB_VUSB") (pintype "bidirectional"))
    )
    (net (code "103") (name "unconnected-(U$2-GND2-PadGND1)") (class "Default")
      (node (ref "U$2") (pin "GND1") (pinfunction "GND2_GND1") (pintype "bidirectional"))
    )
    (net (code "104") (name "unconnected-(U$2-Pad3.3V)") (class "Default")
      (node (ref "U$2") (pin "3.3V") (pinfunction "3.3V_3.3V") (pintype "bidirectional"))
    )
    (net (code "105") (name "unconnected-(U$2-PadA0)") (class "Default")
      (node (ref "U$2") (pin "A0") (pinfunction "A0_A0") (pintype "bidirectional"))
    )
    (net (code "106") (name "unconnected-(U$2-PadA1)") (class "Default")
      (node (ref "U$2") (pin "A1") (pinfunction "A1_A1") (pintype "bidirectional"))
    )
    (net (code "107") (name "unconnected-(U$2-PadA2)") (class "Default")
      (node (ref "U$2") (pin "A2") (pinfunction "A2_A2") (pintype "bidirectional"))
    )
    (net (code "108") (name "unconnected-(U$2-PadA3)") (class "Default")
      (node (ref "U$2") (pin "A3") (pinfunction "A3_A3") (pintype "bidirectional"))
    )
    (net (code "109") (name "unconnected-(U$2-PadA6)") (class "Default")
      (node (ref "U$2") (pin "A6") (pinfunction "A6_A6") (pintype "bidirectional"))
    )
    (net (code "110") (name "unconnected-(U$2-PadA7)") (class "Default")
      (node (ref "U$2") (pin "A7") (pinfunction "A7_A7") (pintype "bidirectional"))
    )
    (net (code "111") (name "unconnected-(U$2-PadAREF)") (class "Default")
      (node (ref "U$2") (pin "AREF") (pinfunction "AREF_AREF") (pintype "bidirectional"))
    )
    (net (code "112") (name "unconnected-(U$2-PadD3)") (class "Default")
      (node (ref "U$2") (pin "D3") (pinfunction "D3_D3") (pintype "bidirectional"))
    )
    (net (code "113") (name "unconnected-(U$2-PadD4)") (class "Default")
      (node (ref "U$2") (pin "D4") (pinfunction "D4_D4") (pintype "bidirectional"))
    )
    (net (code "114") (name "unconnected-(U$2-PadD13)") (class "Default")
      (node (ref "U$2") (pin "D13") (pinfunction "D13_D13") (pintype "bidirectional"))
    )
    (net (code "115") (name "unconnected-(U$2-PadRAW)") (class "Default")
      (node (ref "U$2") (pin "RAW") (pinfunction "RAW_RAW") (pintype "bidirectional"))
    )
    (net (code "116") (name "unconnected-(U$2-PadRST)") (class "Default")
      (node (ref "U$2") (pin "RST") (pinfunction "RST_RST") (pintype "bidirectional"))
    )
    (net (code "117") (name "unconnected-(U$2-PadRST1)") (class "Default")
      (node (ref "U$2") (pin "RST1") (pinfunction "RST1_RST1") (pintype "bidirectional"))
    )
    (net (code "118") (name "unconnected-(U$2-PadRX1)") (class "Default")
      (node (ref "U$2") (pin "RX1") (pinfunction "RX1_RX1") (pintype "bidirectional"))
    )
    (net (code "119") (name "unconnected-(U$2-PadTX0)") (class "Default")
      (node (ref "U$2") (pin "TX0") (pinfunction "TX0_TX0") (pintype "bidirectional"))
    )
    (net (code "120") (name "unconnected-(ULTRA1-Pad3)") (class "Default")
      (node (ref "ULTRA1") (pin "3") (pinfunction "3_3") (pintype "bidirectional"))
    )
    (net (code "121") (name "unconnected-(ULTRA1-Pad4)") (class "Default")
      (node (ref "ULTRA1") (pin "4") (pinfunction "4_4") (pintype "bidirectional"))
    )
    (net (code "122") (name "unconnected-(ULTRA2-Pad3)") (class "Default")
      (node (ref "ULTRA2") (pin "3") (pinfunction "3_3") (pintype "bidirectional"))
    )
    (net (code "123") (name "unconnected-(ULTRA2-Pad4)") (class "Default")
      (node (ref "ULTRA2") (pin "4") (pinfunction "4_4") (pintype "bidirectional"))
    )
    (net (code "124") (name "unconnected-(ULTRA3-Pad3)") (class "Default")
      (node (ref "ULTRA3") (pin "3") (pinfunction "3_3") (pintype "bidirectional"))
    )
    (net (code "125") (name "unconnected-(ULTRA3-Pad4)") (class "Default")
      (node (ref "ULTRA3") (pin "4") (pinfunction "4_4") (pintype "bidirectional"))
    )
    (net (code "126") (name "unconnected-(ULTRA4-Pad3)") (class "Default")
      (node (ref "ULTRA4") (pin "3") (pinfunction "3_3") (pintype "bidirectional"))
    )
    (net (code "127") (name "unconnected-(ULTRA4-Pad4)") (class "Default")
      (node (ref "ULTRA4") (pin "4") (pinfunction "4_4") (pintype "bidirectional"))
    )
  )
)
